# ADC.net
KiCad netlist of a schematic drawn in Altium Designer
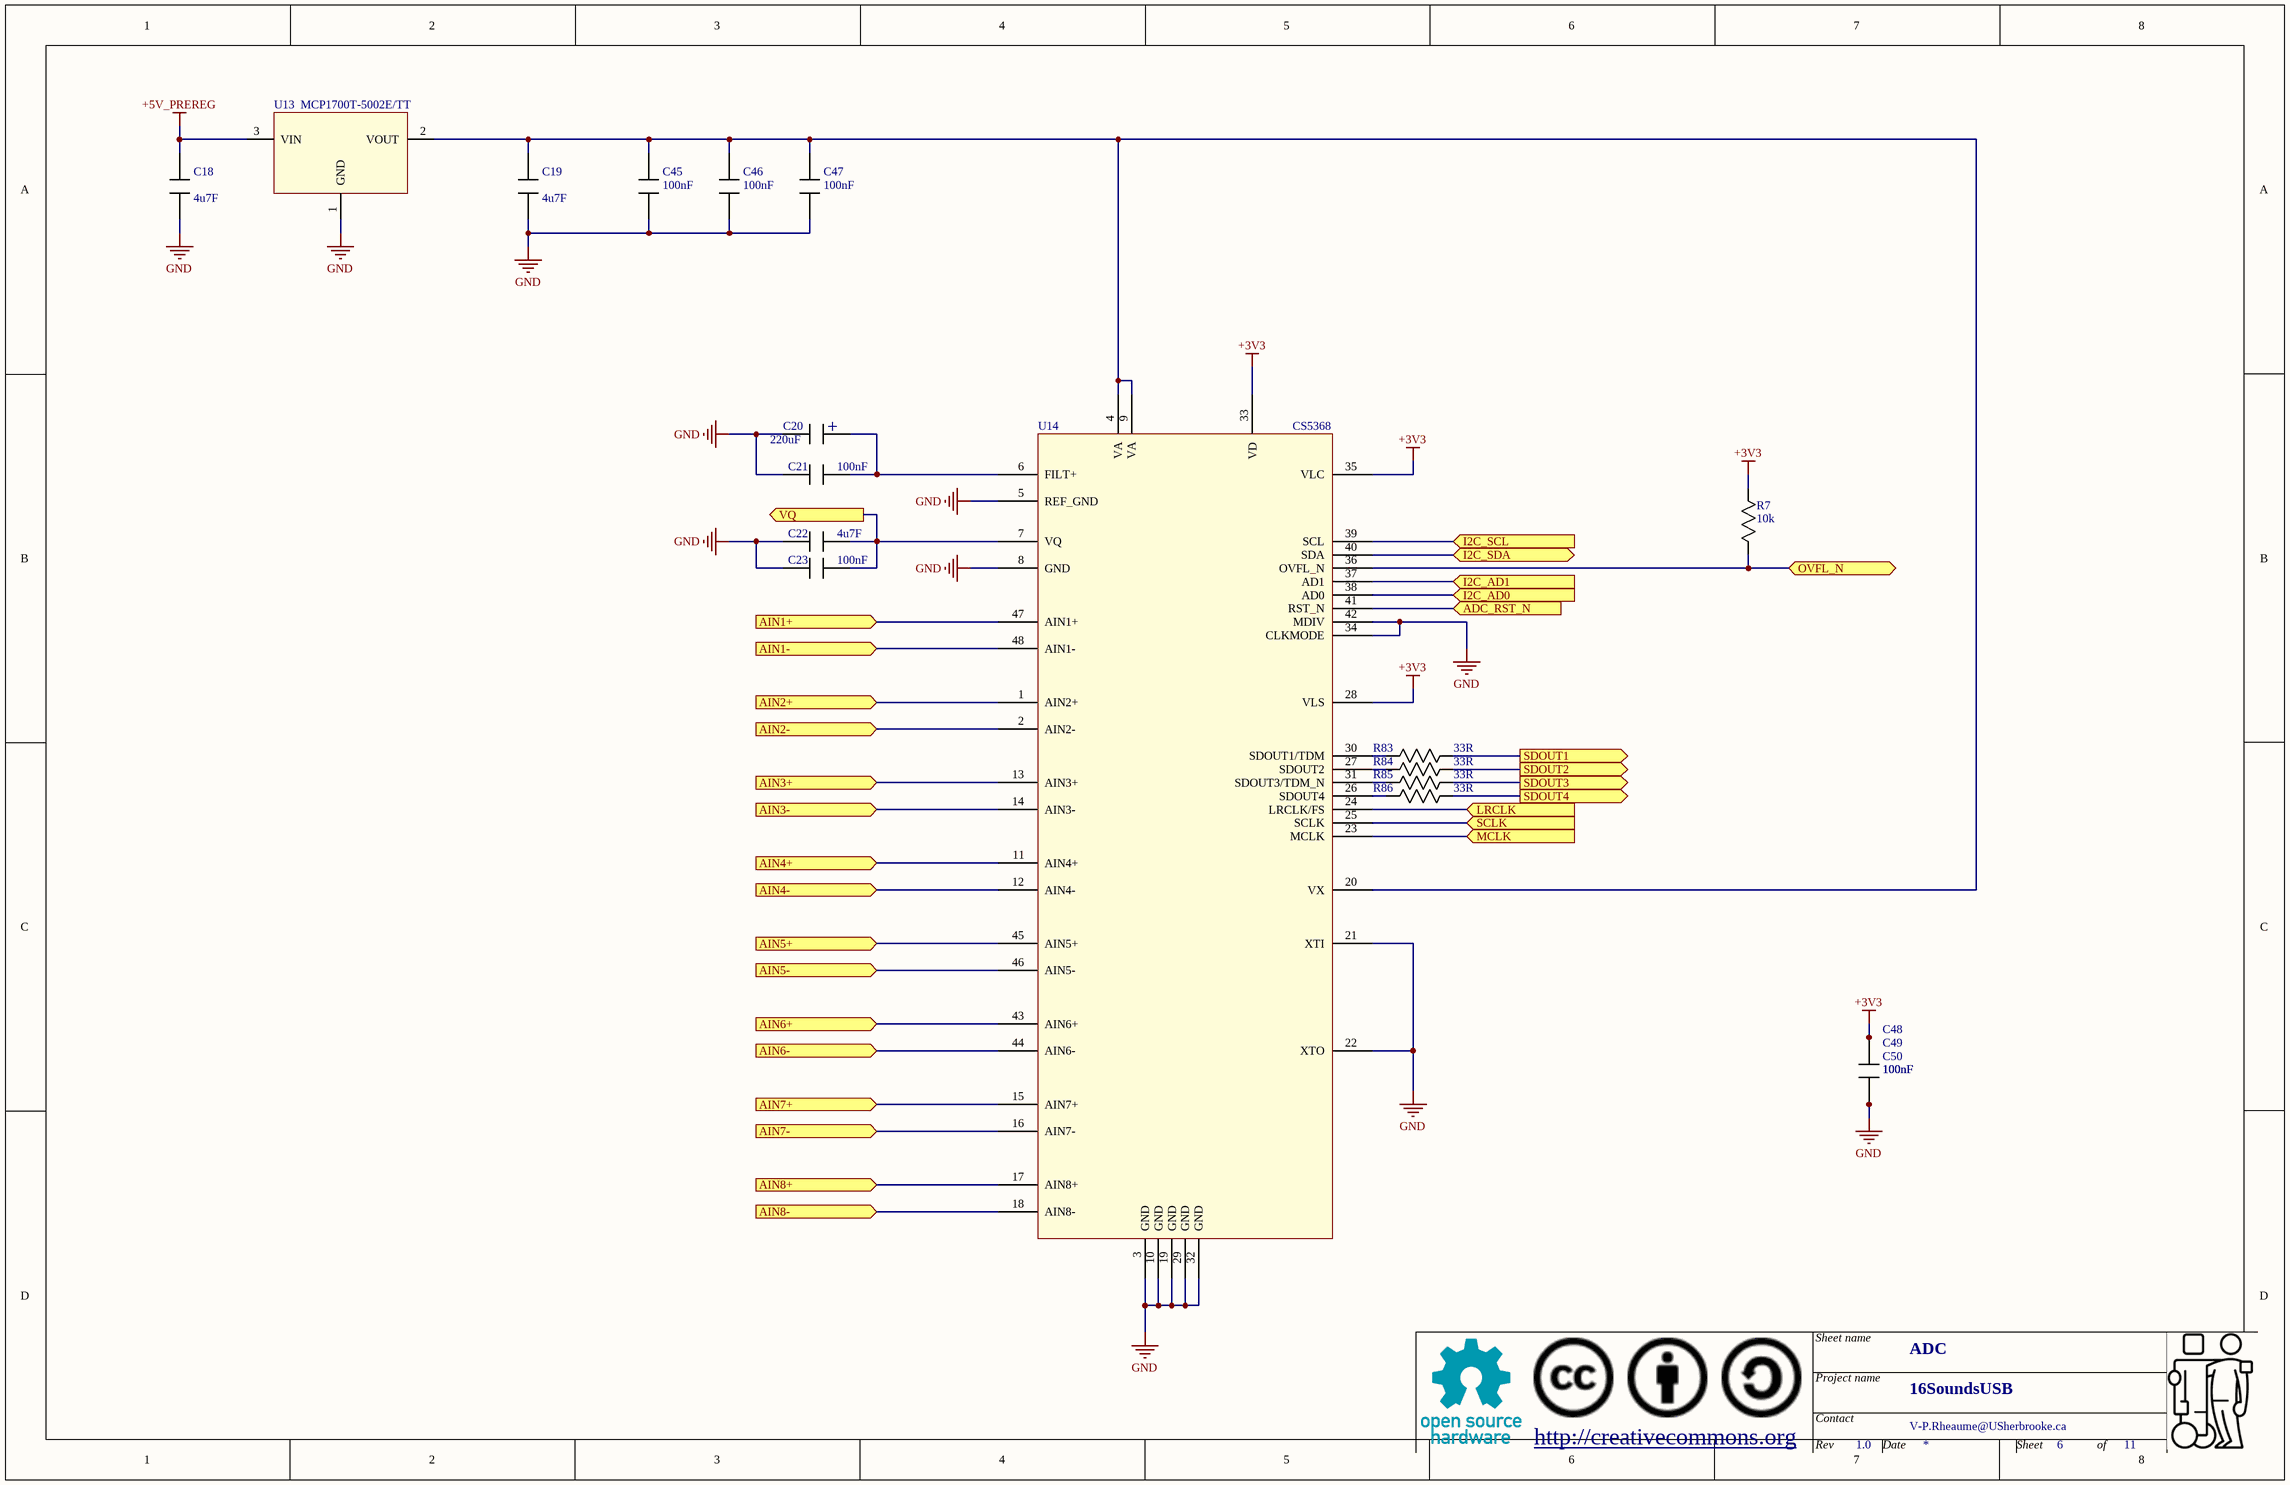
[diagram p0: ADC.SchDoc]

(export (version "E")
  (design (tool "Eeschema 10.0.6"))
  (components
    (comp (ref "C18")
      (value "4u7F")
      (footprint "0805")
      (description "Capacitor")
      (fields (field (name "MFG") "Samsung"))
      (libsource (lib "INTER_2014") (part "Capacitor"))
    )
    (comp (ref "C19")
      (value "4u7F")
      (footprint "0805")
      (description "Capacitor")
      (fields (field (name "MFG") "Samsung"))
      (libsource (lib "INTER_2014") (part "Capacitor"))
    )
    (comp (ref "C20")
      (value "220uF")
      (footprint "CAP_RAD_SMD_DIA315")
      (description "Capacitor")
      (fields (field (name "MFG") "Nichicon") (field (name "Comment") "Capacitor_Polarized"))
      (libsource (lib "INTER_2014") (part "Capacitor_Polarized"))
    )
    (comp (ref "C21")
      (value "100nF")
      (footprint "0603")
      (description "Capacitor")
      (fields (field (name "MFG") "Samsung"))
      (libsource (lib "INTER_2014") (part "Capacitor"))
    )
    (comp (ref "C22")
      (value "4u7F")
      (footprint "0805")
      (description "Capacitor")
      (fields (field (name "MFG") "Samsung"))
      (libsource (lib "INTER_2014") (part "Capacitor"))
    )
    (comp (ref "C23")
      (value "100nF")
      (footprint "0603")
      (description "Capacitor")
      (fields (field (name "MFG") "Samsung"))
      (libsource (lib "INTER_2014") (part "Capacitor"))
    )
    (comp (ref "C45")
      (value "100nF")
      (footprint "0603")
      (description "Capacitor")
      (fields (field (name "MFG") "Samsung"))
      (libsource (lib "INTER_2014") (part "Capacitor"))
    )
    (comp (ref "C46")
      (value "100nF")
      (footprint "0603")
      (description "Capacitor")
      (fields (field (name "MFG") "Samsung"))
      (libsource (lib "INTER_2014") (part "Capacitor"))
    )
    (comp (ref "C47")
      (value "100nF")
      (footprint "0603")
      (description "Capacitor")
      (fields (field (name "MFG") "Samsung"))
      (libsource (lib "INTER_2014") (part "Capacitor"))
    )
    (comp (ref "C48")
      (value "100nF")
      (footprint "0603")
      (description "Capacitor")
      (fields (field (name "MFG") "Samsung"))
      (libsource (lib "INTER_2014") (part "Capacitor"))
    )
    (comp (ref "C49")
      (value "100nF")
      (footprint "0603")
      (description "Capacitor")
      (fields (field (name "MFG") "Samsung"))
      (libsource (lib "INTER_2014") (part "Capacitor"))
    )
    (comp (ref "C50")
      (value "100nF")
      (footprint "0603")
      (description "Capacitor")
      (fields (field (name "MFG") "Samsung"))
      (libsource (lib "INTER_2014") (part "Capacitor"))
    )
    (comp (ref "R7")
      (value "10k")
      (footprint "0603")
      (description "Resistor")
      (fields (field (name "MFG") "Yageo"))
      (libsource (lib "INTER_2014") (part "Resistor"))
    )
    (comp (ref "R83")
      (value "33R")
      (footprint "0603")
      (description "Resistor")
      (fields (field (name "MFG") "Yageo"))
      (libsource (lib "INTER_2014") (part "Resistor"))
    )
    (comp (ref "R84")
      (value "33R")
      (footprint "0603")
      (description "Resistor")
      (fields (field (name "MFG") "Yageo"))
      (libsource (lib "INTER_2014") (part "Resistor"))
    )
    (comp (ref "R85")
      (value "33R")
      (footprint "0603")
      (description "Resistor")
      (fields (field (name "MFG") "Yageo"))
      (libsource (lib "INTER_2014") (part "Resistor"))
    )
    (comp (ref "R86")
      (value "33R")
      (footprint "0603")
      (description "Resistor")
      (fields (field (name "MFG") "Yageo"))
      (libsource (lib "INTER_2014") (part "Resistor"))
    )
    (comp (ref "U13")
      (value "MCP1700")
      (footprint "SOT23_132")
      (description "Linear voltage regulator")
      (fields (field (name "MFG") "Microchip") (field (name "MFG_PN") "MCP1700T-5002E/TT"))
      (libsource (lib "INTER_2014") (part "MCP1700"))
    )
    (comp (ref "U14")
      (value "CS5368")
      (footprint "LQFP_48L_CIRRUS")
      (description "ADC, 24bit, 8 chan, 192kHz, PCM, TDM, LQFP48")
      (fields (field (name "MFG") "Cirrus"))
      (libsource (lib "INTER_2014") (part "CS5368"))
    )
  )
  (nets
    (net (code "1") (name "+3V3") (class "Default")
      (node (ref "C48") (pin "1") (pintype "passive"))
      (node (ref "C49") (pin "1") (pintype "passive"))
      (node (ref "C50") (pin "1") (pintype "passive"))
      (node (ref "R7") (pin "1") (pintype "passive"))
      (node (ref "U14") (pin "28") (pinfunction "VLS_28") (pintype "passive"))
      (node (ref "U14") (pin "33") (pinfunction "VD_33") (pintype "passive"))
      (node (ref "U14") (pin "35") (pinfunction "VLC_35") (pintype "passive"))
    )
    (net (code "2") (name "+5V_PREREG") (class "Default")
      (node (ref "C18") (pin "1") (pintype "passive"))
      (node (ref "U13") (pin "3") (pinfunction "VIN_3") (pintype "passive"))
    )
    (net (code "3") (name "/ADC_RST_N") (class "Default")
      (node (ref "U14") (pin "41") (pinfunction "RST_N_41") (pintype "passive"))
    )
    (net (code "4") (name "/AIN1+") (class "Default")
      (node (ref "U14") (pin "47") (pinfunction "AIN1+_47") (pintype "passive"))
    )
    (net (code "5") (name "/AIN1-") (class "Default")
      (node (ref "U14") (pin "48") (pinfunction "AIN1-_48") (pintype "passive"))
    )
    (net (code "6") (name "/AIN2+") (class "Default")
      (node (ref "U14") (pin "1") (pinfunction "AIN2+_1") (pintype "passive"))
    )
    (net (code "7") (name "/AIN2-") (class "Default")
      (node (ref "U14") (pin "2") (pinfunction "AIN2-_2") (pintype "passive"))
    )
    (net (code "8") (name "/AIN3+") (class "Default")
      (node (ref "U14") (pin "13") (pinfunction "AIN3+_13") (pintype "passive"))
    )
    (net (code "9") (name "/AIN3-") (class "Default")
      (node (ref "U14") (pin "14") (pinfunction "AIN3-_14") (pintype "passive"))
    )
    (net (code "10") (name "/AIN4+") (class "Default")
      (node (ref "U14") (pin "11") (pinfunction "AIN4+_11") (pintype "passive"))
    )
    (net (code "11") (name "/AIN4-") (class "Default")
      (node (ref "U14") (pin "12") (pinfunction "AIN4-_12") (pintype "passive"))
    )
    (net (code "12") (name "/AIN5+") (class "Default")
      (node (ref "U14") (pin "45") (pinfunction "AIN5+_45") (pintype "passive"))
    )
    (net (code "13") (name "/AIN5-") (class "Default")
      (node (ref "U14") (pin "46") (pinfunction "AIN5-_46") (pintype "passive"))
    )
    (net (code "14") (name "/AIN6+") (class "Default")
      (node (ref "U14") (pin "43") (pinfunction "AIN6+_43") (pintype "passive"))
    )
    (net (code "15") (name "/AIN6-") (class "Default")
      (node (ref "U14") (pin "44") (pinfunction "AIN6-_44") (pintype "passive"))
    )
    (net (code "16") (name "/AIN7+") (class "Default")
      (node (ref "U14") (pin "15") (pinfunction "AIN7+_15") (pintype "passive"))
    )
    (net (code "17") (name "/AIN7-") (class "Default")
      (node (ref "U14") (pin "16") (pinfunction "AIN7-_16") (pintype "passive"))
    )
    (net (code "18") (name "/AIN8+") (class "Default")
      (node (ref "U14") (pin "17") (pinfunction "AIN8+_17") (pintype "passive"))
    )
    (net (code "19") (name "/AIN8-") (class "Default")
      (node (ref "U14") (pin "18") (pinfunction "AIN8-_18") (pintype "passive"))
    )
    (net (code "20") (name "/I2C_AD0") (class "Default")
      (node (ref "U14") (pin "38") (pinfunction "AD0_38") (pintype "passive"))
    )
    (net (code "21") (name "/I2C_AD1") (class "Default")
      (node (ref "U14") (pin "37") (pinfunction "AD1_37") (pintype "passive"))
    )
    (net (code "22") (name "/I2C_SCL") (class "Default")
      (node (ref "U14") (pin "39") (pinfunction "SCL_39") (pintype "passive"))
    )
    (net (code "23") (name "/I2C_SDA") (class "Default")
      (node (ref "U14") (pin "40") (pinfunction "SDA_40") (pintype "passive"))
    )
    (net (code "24") (name "/LRCLK") (class "Default")
      (node (ref "U14") (pin "24") (pinfunction "LRCLK/FS_24") (pintype "passive"))
    )
    (net (code "25") (name "/MCLK") (class "Default")
      (node (ref "U14") (pin "23") (pinfunction "MCLK_23") (pintype "passive"))
    )
    (net (code "26") (name "/OVFL_N") (class "Default")
      (node (ref "R7") (pin "2") (pintype "passive"))
      (node (ref "U14") (pin "36") (pinfunction "OVFL_N_36") (pintype "passive"))
    )
    (net (code "27") (name "/SCLK") (class "Default")
      (node (ref "U14") (pin "25") (pinfunction "SCLK_25") (pintype "passive"))
    )
    (net (code "28") (name "/SDOUT1") (class "Default") (node (ref "R83") (pin "2") (pintype "passive")))
    (net (code "29") (name "/SDOUT2") (class "Default") (node (ref "R84") (pin "2") (pintype "passive")))
    (net (code "30") (name "/SDOUT3") (class "Default") (node (ref "R85") (pin "2") (pintype "passive")))
    (net (code "31") (name "/SDOUT4") (class "Default") (node (ref "R86") (pin "2") (pintype "passive")))
    (net (code "32") (name "/VQ") (class "Default")
      (node (ref "C22") (pin "1") (pintype "passive"))
      (node (ref "C23") (pin "1") (pintype "passive"))
      (node (ref "U14") (pin "7") (pinfunction "VQ_7") (pintype "passive"))
    )
    (net (code "33") (name "GND") (class "Default")
      (node (ref "C18") (pin "2") (pintype "passive"))
      (node (ref "C19") (pin "2") (pintype "passive"))
      (node (ref "C20") (pin "-") (pintype "passive"))
      (node (ref "C21") (pin "2") (pintype "passive"))
      (node (ref "C22") (pin "2") (pintype "passive"))
      (node (ref "C23") (pin "2") (pintype "passive"))
      (node (ref "C45") (pin "2") (pintype "passive"))
      (node (ref "C46") (pin "2") (pintype "passive"))
      (node (ref "C47") (pin "2") (pintype "passive"))
      (node (ref "C48") (pin "2") (pintype "passive"))
      (node (ref "C49") (pin "2") (pintype "passive"))
      (node (ref "C50") (pin "2") (pintype "passive"))
      (node (ref "U13") (pin "1") (pinfunction "GND_1") (pintype "passive"))
      (node (ref "U14") (pin "10") (pinfunction "GND_10") (pintype "passive"))
      (node (ref "U14") (pin "19") (pinfunction "GND_19") (pintype "passive"))
      (node (ref "U14") (pin "21") (pinfunction "XTI_21") (pintype "passive"))
      (node (ref "U14") (pin "22") (pinfunction "XTO_22") (pintype "passive"))
      (node (ref "U14") (pin "29") (pinfunction "GND_29") (pintype "passive"))
      (node (ref "U14") (pin "3") (pinfunction "GND_3") (pintype "passive"))
      (node (ref "U14") (pin "32") (pinfunction "GND_32") (pintype "passive"))
      (node (ref "U14") (pin "34") (pinfunction "CLKMODE_34") (pintype "passive"))
      (node (ref "U14") (pin "42") (pinfunction "MDIV_42") (pintype "passive"))
      (node (ref "U14") (pin "5") (pinfunction "REF_GND_5") (pintype "passive"))
      (node (ref "U14") (pin "8") (pinfunction "GND_8") (pintype "passive"))
    )
    (net (code "34") (name "Net-(U13-VOUT)") (class "Default")
      (node (ref "C19") (pin "1") (pintype "passive"))
      (node (ref "C45") (pin "1") (pintype "passive"))
      (node (ref "C46") (pin "1") (pintype "passive"))
      (node (ref "C47") (pin "1") (pintype "passive"))
      (node (ref "U13") (pin "2") (pinfunction "VOUT_2") (pintype "passive"))
      (node (ref "U14") (pin "20") (pinfunction "VX_20") (pintype "passive"))
      (node (ref "U14") (pin "4") (pinfunction "VA_4") (pintype "passive"))
      (node (ref "U14") (pin "9") (pinfunction "VA_9") (pintype "passive"))
    )
    (net (code "35") (name "Net-(U14-FILT+)") (class "Default")
      (node (ref "C20") (pin "+") (pintype "passive"))
      (node (ref "C21") (pin "1") (pintype "passive"))
      (node (ref "U14") (pin "6") (pinfunction "FILT+_6") (pintype "passive"))
    )
    (net (code "36") (name "Net-(U14-SDOUT1{slash}TDM)") (class "Default")
      (node (ref "R83") (pin "1") (pintype "passive"))
      (node (ref "U14") (pin "30") (pinfunction "SDOUT1/TDM_30") (pintype "passive"))
    )
    (net (code "37") (name "Net-(U14-SDOUT2)") (class "Default")
      (node (ref "R84") (pin "1") (pintype "passive"))
      (node (ref "U14") (pin "27") (pinfunction "SDOUT2_27") (pintype "passive"))
    )
    (net (code "38") (name "Net-(U14-SDOUT3{slash}TDM_N)") (class "Default")
      (node (ref "R85") (pin "1") (pintype "passive"))
      (node (ref "U14") (pin "31") (pinfunction "SDOUT3/TDM_N_31") (pintype "passive"))
    )
    (net (code "39") (name "Net-(U14-SDOUT4)") (class "Default")
      (node (ref "R86") (pin "1") (pintype "passive"))
      (node (ref "U14") (pin "26") (pinfunction "SDOUT4_26") (pintype "passive"))
    )
  )
)
